# Comparator.net
KiCad netlist of a schematic drawn in EAGLE
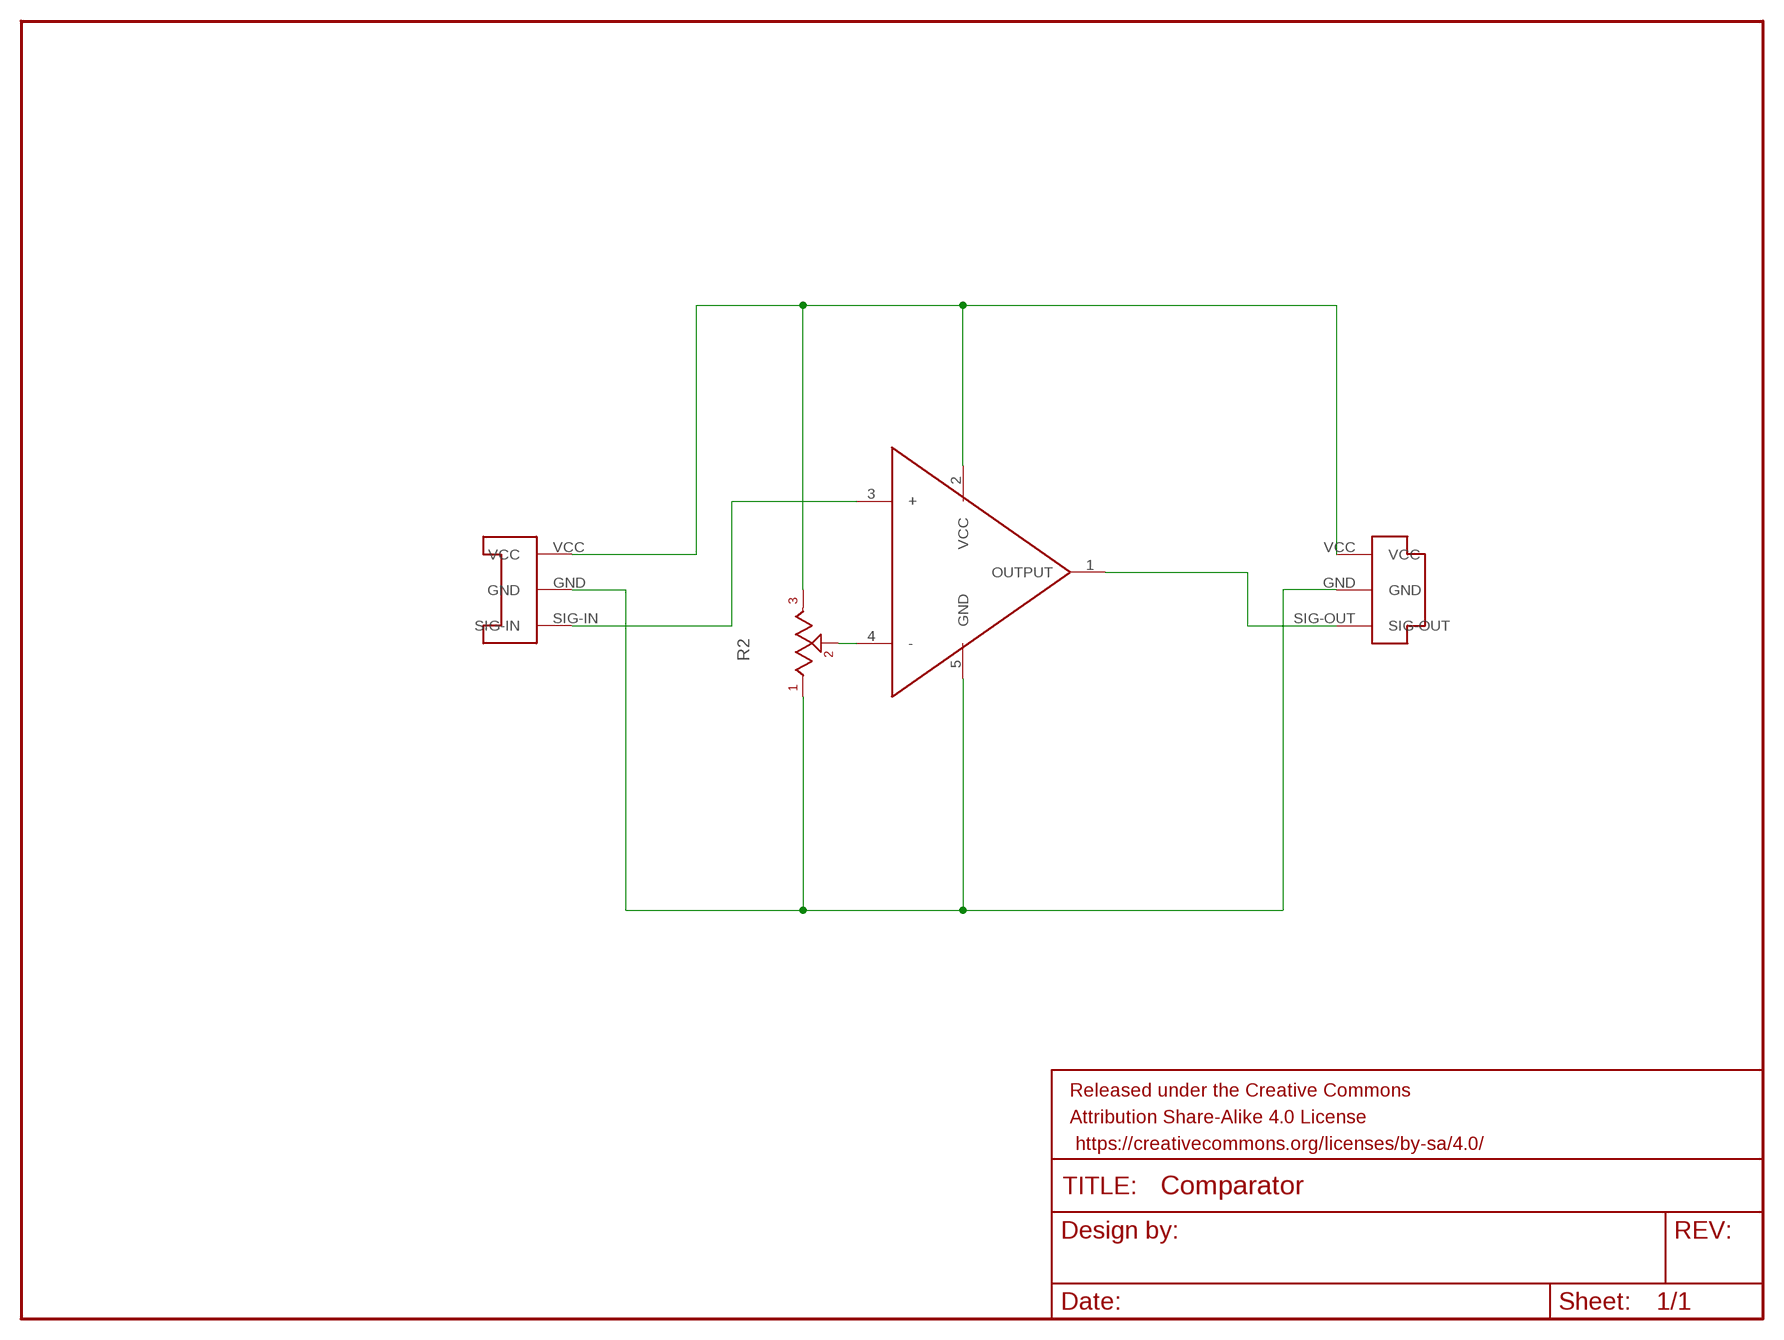
[diagram p0: schematic, sheet 1]

(export (version "E")
  (design (tool "Eeschema 10.0.6"))
  (components
    (comp (ref "FRAME1")
      (value "FRAME-LETTERNO_PACKAGE")
      (footprint "eagle-import:DUMMY")
      (fields (field (name "DESIGNER") "Nobody"))
      (libsource (lib "eagle-import") (part "FRAME-LETTERNO_PACKAGE"))
    )
    (comp (ref "R2")
      (value "POT-TRIM-SMD-BOURNS-3314J-1")
      (footprint "eagle-import:POT-TRIM-SMD-BOURNS-3314")
      (libsource (lib "eagle-import") (part "POT-TRIM-SMD-BOURNS-3314J-1"))
    )
    (comp (ref "U$1")
      (value "CONN-PLUG-3POS-3MM")
      (footprint "eagle-import:PLUG-3POS-3MM-SMD")
      (libsource (lib "eagle-import") (part "CONN-PLUG-3POS-3MM"))
    )
    (comp (ref "U$2")
      (value "CONN-SOCKET-3POS-3MM")
      (footprint "eagle-import:SOCKET-3POS-3MM-SMD")
      (libsource (lib "eagle-import") (part "CONN-SOCKET-3POS-3MM"))
    )
    (comp (ref "U$3")
      (value "COMPARATOR-NCS2200")
      (footprint "eagle-import:SOT23-5")
      (libsource (lib "eagle-import") (part "COMPARATOR-NCS2200"))
    )
  )
  (nets
    (net (code "1") (name "Net-(R2-1)") (class "Default")
      (node (ref "R2") (pin "3") (pinfunction "1_3") (pintype "passive"))
      (node (ref "U$1") (pin "GND") (pinfunction "GND_GND") (pintype "power_in"))
      (node (ref "U$2") (pin "GND") (pinfunction "GND_GND") (pintype "power_in"))
      (node (ref "U$3") (pin "5") (pinfunction "GND_5") (pintype "power_in"))
    )
    (net (code "2") (name "Net-(R2-3)") (class "Default")
      (node (ref "R2") (pin "1") (pinfunction "3_1") (pintype "passive"))
      (node (ref "U$1") (pin "VCC") (pinfunction "VCC_VCC") (pintype "power_in"))
      (node (ref "U$2") (pin "VCC") (pinfunction "VCC_VCC") (pintype "power_in"))
      (node (ref "U$3") (pin "2") (pinfunction "VCC_2") (pintype "power_in"))
    )
    (net (code "3") (name "Net-(U$3-+)") (class "Default")
      (node (ref "U$2") (pin "SIG-IN") (pinfunction "SIG-IN_SIG-IN") (pintype "bidirectional"))
      (node (ref "U$3") (pin "3") (pinfunction "+_3") (pintype "input"))
    )
    (net (code "4") (name "Net-(U$3--)") (class "Default")
      (node (ref "R2") (pin "2") (pinfunction "2_2") (pintype "passive"))
      (node (ref "U$3") (pin "4") (pinfunction "-_4") (pintype "input"))
    )
    (net (code "5") (name "Net-(U$3-OUTPUT)") (class "Default")
      (node (ref "U$1") (pin "SIG-OUT") (pinfunction "SIG-OUT_SIG-OUT") (pintype "bidirectional"))
      (node (ref "U$3") (pin "1") (pinfunction "OUTPUT_1") (pintype "output"))
    )
  )
)
